# Ctrl_main10.net
KiCad netlist of a schematic drawn in EAGLE
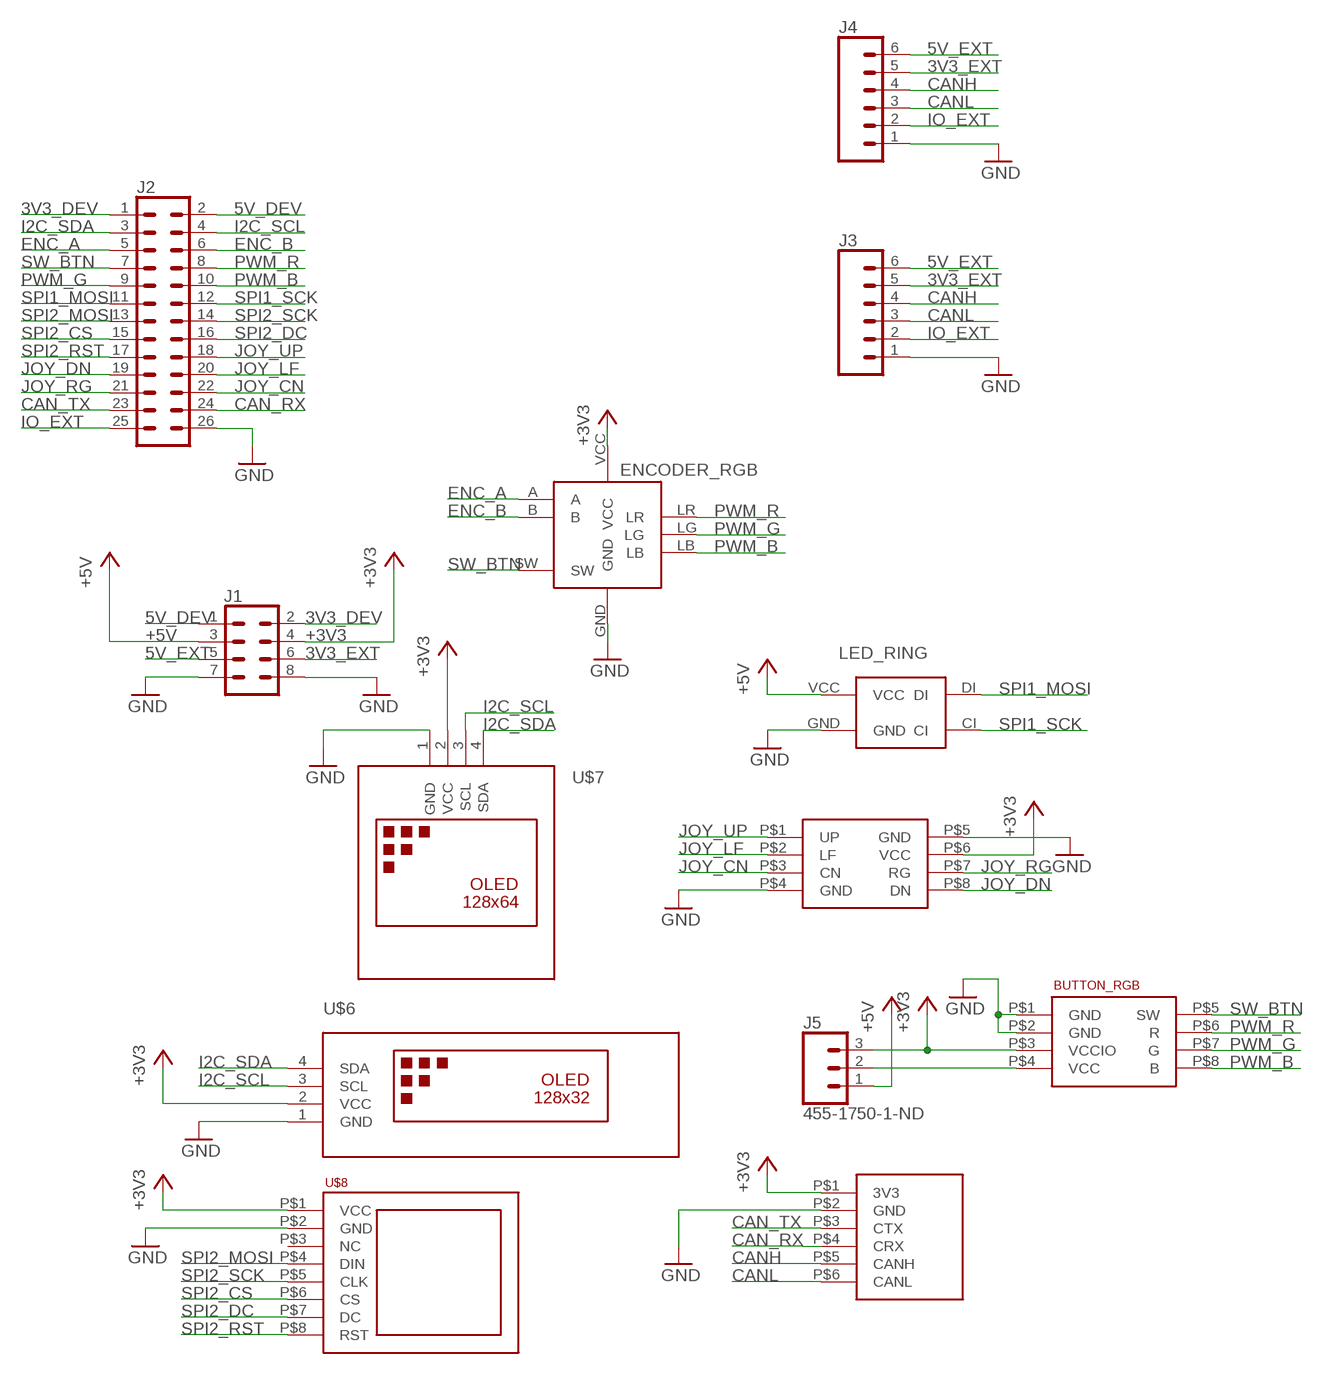
[diagram p0: schematic, sheet 1]

(export (version "E")
  (design (tool "Eeschema 10.0.6"))
  (components
    (comp (ref "BUTTON_RGB")
      (value "CTRL_BTNRGB_BRD")
      (footprint "eagle-import:CTRL_BTNRGB_BRD")
      (libsource (lib "eagle-import") (part "CTRL_BTNRGB_BRD"))
    )
    (comp (ref "ENCODER_RGB")
      (value "CTRL_ENC")
      (footprint "eagle-import:CTRL_ENC")
      (libsource (lib "eagle-import") (part "CTRL_ENC"))
    )
    (comp (ref "J1")
      (value "CONN_04X2")
      (footprint "eagle-import:2X4")
      (libsource (lib "eagle-import") (part "CONN_04X2"))
    )
    (comp (ref "J2")
      (value "CONN_13X22X13")
      (footprint "eagle-import:2X13")
      (libsource (lib "eagle-import") (part "CONN_13X22X13"))
    )
    (comp (ref "J3")
      (value "CONN_06SILK_FEMALE_PTH")
      (footprint "eagle-import:1X06")
      (libsource (lib "eagle-import") (part "CONN_06SILK_FEMALE_PTH"))
    )
    (comp (ref "J4")
      (value "CONN_06SILK_FEMALE_PTH")
      (footprint "eagle-import:1X06")
      (libsource (lib "eagle-import") (part "CONN_06SILK_FEMALE_PTH"))
    )
    (comp (ref "J5")
      (value "455-1750-1-ND")
      (footprint "eagle-import:1X03")
      (libsource (lib "eagle-import") (part "CONN_03"))
    )
    (comp (ref "LED_RING")
      (value "CTRL_RING")
      (footprint "eagle-import:CTRL_RING")
      (libsource (lib "eagle-import") (part "CTRL_RING"))
    )
    (comp (ref "U$3")
      (value "CTRL_JOY")
      (footprint "eagle-import:CTRL_JOY")
      (libsource (lib "eagle-import") (part "CTRL_JOY"))
    )
    (comp (ref "U$4")
      (value "CTRL_CAN")
      (footprint "eagle-import:CTRL_CAN")
      (libsource (lib "eagle-import") (part "CTRL_CAN"))
    )
    (comp (ref "U$6")
      (value "DISPLAY-OLED-128X32")
      (footprint "eagle-import:DISPLAY-OLED-128X32")
      (libsource (lib "eagle-import") (part "DISPLAY-OLED-128X32"))
    )
    (comp (ref "U$7")
      (value "DISPLAY-OLED-128X64-I2C")
      (footprint "eagle-import:DISPLAY-OLED-128X64-I2C")
      (libsource (lib "eagle-import") (part "DISPLAY-OLED-128X64-I2C"))
    )
    (comp (ref "U$8")
      (value "OLED_WS128")
      (footprint "eagle-import:OLED_WS128")
      (libsource (lib "eagle-import") (part "OLED_WS128"))
    )
  )
  (nets
    (net (code "1") (name "+3V3") (class "Default")
      (node (ref "BUTTON_RGB") (pin "P$3") (pinfunction "VCCIO_P$3") (pintype "bidirectional"))
      (node (ref "ENCODER_RGB") (pin "VCC") (pinfunction "VCC_VCC") (pintype "bidirectional"))
      (node (ref "J1") (pin "4") (pinfunction "4_4") (pintype "passive"))
      (node (ref "J5") (pin "3") (pinfunction "3_3") (pintype "passive"))
      (node (ref "U$3") (pin "P$6") (pinfunction "VCC_P$6") (pintype "bidirectional"))
      (node (ref "U$4") (pin "P$1") (pinfunction "3V3_P$1") (pintype "bidirectional"))
      (node (ref "U$6") (pin "2") (pinfunction "VCC_2") (pintype "power_in"))
      (node (ref "U$7") (pin "2") (pinfunction "VCC_2") (pintype "power_in"))
      (node (ref "U$8") (pin "P$1") (pinfunction "VCC_P$1") (pintype "bidirectional"))
    )
    (net (code "2") (name "+5V") (class "Default")
      (node (ref "J1") (pin "3") (pinfunction "3_3") (pintype "passive"))
      (node (ref "J5") (pin "1") (pinfunction "1_1") (pintype "passive"))
      (node (ref "LED_RING") (pin "VCC") (pinfunction "VCC_VCC") (pintype "bidirectional"))
    )
    (net (code "3") (name "/3V3_DEV") (class "Default")
      (node (ref "J1") (pin "2") (pinfunction "2_2") (pintype "passive"))
      (node (ref "J2") (pin "1") (pinfunction "1_1") (pintype "passive"))
    )
    (net (code "4") (name "/3V3_EXT") (class "Default")
      (node (ref "J1") (pin "6") (pinfunction "6_6") (pintype "passive"))
      (node (ref "J3") (pin "5") (pinfunction "5_5") (pintype "passive"))
      (node (ref "J4") (pin "5") (pinfunction "5_5") (pintype "passive"))
    )
    (net (code "5") (name "/5V_DEV") (class "Default")
      (node (ref "J1") (pin "1") (pinfunction "1_1") (pintype "passive"))
      (node (ref "J2") (pin "2") (pinfunction "2_2") (pintype "passive"))
    )
    (net (code "6") (name "/5V_EXT") (class "Default")
      (node (ref "J1") (pin "5") (pinfunction "5_5") (pintype "passive"))
      (node (ref "J3") (pin "6") (pinfunction "6_6") (pintype "passive"))
      (node (ref "J4") (pin "6") (pinfunction "6_6") (pintype "passive"))
    )
    (net (code "7") (name "/CANH") (class "Default")
      (node (ref "J3") (pin "4") (pinfunction "4_4") (pintype "passive"))
      (node (ref "J4") (pin "4") (pinfunction "4_4") (pintype "passive"))
      (node (ref "U$4") (pin "P$5") (pinfunction "CANH_P$5") (pintype "bidirectional"))
    )
    (net (code "8") (name "/CANL") (class "Default")
      (node (ref "J3") (pin "3") (pinfunction "3_3") (pintype "passive"))
      (node (ref "J4") (pin "3") (pinfunction "3_3") (pintype "passive"))
      (node (ref "U$4") (pin "P$6") (pinfunction "CANL_P$6") (pintype "bidirectional"))
    )
    (net (code "9") (name "/CAN_RX") (class "Default")
      (node (ref "J2") (pin "24") (pinfunction "24_24") (pintype "passive"))
      (node (ref "U$4") (pin "P$4") (pinfunction "CRX_P$4") (pintype "bidirectional"))
    )
    (net (code "10") (name "/CAN_TX") (class "Default")
      (node (ref "J2") (pin "23") (pinfunction "23_23") (pintype "passive"))
      (node (ref "U$4") (pin "P$3") (pinfunction "CTX_P$3") (pintype "bidirectional"))
    )
    (net (code "11") (name "/ENC_A") (class "Default")
      (node (ref "ENCODER_RGB") (pin "A") (pinfunction "A_A") (pintype "bidirectional"))
      (node (ref "J2") (pin "5") (pinfunction "5_5") (pintype "passive"))
    )
    (net (code "12") (name "/ENC_B") (class "Default")
      (node (ref "ENCODER_RGB") (pin "B") (pinfunction "B_B") (pintype "bidirectional"))
      (node (ref "J2") (pin "6") (pinfunction "6_6") (pintype "passive"))
    )
    (net (code "13") (name "/I2C_SCL") (class "Default")
      (node (ref "J2") (pin "4") (pinfunction "4_4") (pintype "passive"))
      (node (ref "U$6") (pin "3") (pinfunction "SCL_3") (pintype "bidirectional"))
      (node (ref "U$7") (pin "3") (pinfunction "SCL_3") (pintype "bidirectional"))
    )
    (net (code "14") (name "/I2C_SDA") (class "Default")
      (node (ref "J2") (pin "3") (pinfunction "3_3") (pintype "passive"))
      (node (ref "U$6") (pin "4") (pinfunction "SDA_4") (pintype "bidirectional"))
      (node (ref "U$7") (pin "4") (pinfunction "SDA_4") (pintype "bidirectional"))
    )
    (net (code "15") (name "/IO_EXT") (class "Default")
      (node (ref "J2") (pin "25") (pinfunction "25_25") (pintype "passive"))
      (node (ref "J3") (pin "2") (pinfunction "2_2") (pintype "passive"))
      (node (ref "J4") (pin "2") (pinfunction "2_2") (pintype "passive"))
    )
    (net (code "16") (name "/JOY_CN") (class "Default")
      (node (ref "J2") (pin "22") (pinfunction "22_22") (pintype "passive"))
      (node (ref "U$3") (pin "P$3") (pinfunction "CN_P$3") (pintype "bidirectional"))
    )
    (net (code "17") (name "/JOY_DN") (class "Default")
      (node (ref "J2") (pin "19") (pinfunction "19_19") (pintype "passive"))
      (node (ref "U$3") (pin "P$8") (pinfunction "DN_P$8") (pintype "bidirectional"))
    )
    (net (code "18") (name "/JOY_LF") (class "Default")
      (node (ref "J2") (pin "20") (pinfunction "20_20") (pintype "passive"))
      (node (ref "U$3") (pin "P$2") (pinfunction "LF_P$2") (pintype "bidirectional"))
    )
    (net (code "19") (name "/JOY_RG") (class "Default")
      (node (ref "J2") (pin "21") (pinfunction "21_21") (pintype "passive"))
      (node (ref "U$3") (pin "P$7") (pinfunction "RG_P$7") (pintype "bidirectional"))
    )
    (net (code "20") (name "/JOY_UP") (class "Default")
      (node (ref "J2") (pin "18") (pinfunction "18_18") (pintype "passive"))
      (node (ref "U$3") (pin "P$1") (pinfunction "UP_P$1") (pintype "bidirectional"))
    )
    (net (code "21") (name "/PWM_B") (class "Default")
      (node (ref "BUTTON_RGB") (pin "P$8") (pinfunction "B_P$8") (pintype "bidirectional"))
      (node (ref "ENCODER_RGB") (pin "LB") (pinfunction "LB_LB") (pintype "bidirectional"))
      (node (ref "J2") (pin "10") (pinfunction "10_10") (pintype "passive"))
    )
    (net (code "22") (name "/PWM_G") (class "Default")
      (node (ref "BUTTON_RGB") (pin "P$7") (pinfunction "G_P$7") (pintype "bidirectional"))
      (node (ref "ENCODER_RGB") (pin "LG") (pinfunction "LG_LG") (pintype "bidirectional"))
      (node (ref "J2") (pin "9") (pinfunction "9_9") (pintype "passive"))
    )
    (net (code "23") (name "/PWM_R") (class "Default")
      (node (ref "BUTTON_RGB") (pin "P$6") (pinfunction "R_P$6") (pintype "bidirectional"))
      (node (ref "ENCODER_RGB") (pin "LR") (pinfunction "LR_LR") (pintype "bidirectional"))
      (node (ref "J2") (pin "8") (pinfunction "8_8") (pintype "passive"))
    )
    (net (code "24") (name "/SPI1_MOSI") (class "Default")
      (node (ref "J2") (pin "11") (pinfunction "11_11") (pintype "passive"))
      (node (ref "LED_RING") (pin "DI") (pinfunction "DI_DI") (pintype "bidirectional"))
    )
    (net (code "25") (name "/SPI1_SCK") (class "Default")
      (node (ref "J2") (pin "12") (pinfunction "12_12") (pintype "passive"))
      (node (ref "LED_RING") (pin "CI") (pinfunction "CI_CI") (pintype "bidirectional"))
    )
    (net (code "26") (name "/SPI2_CS") (class "Default")
      (node (ref "J2") (pin "15") (pinfunction "15_15") (pintype "passive"))
      (node (ref "U$8") (pin "P$6") (pinfunction "CS_P$6") (pintype "bidirectional"))
    )
    (net (code "27") (name "/SPI2_DC") (class "Default")
      (node (ref "J2") (pin "16") (pinfunction "16_16") (pintype "passive"))
      (node (ref "U$8") (pin "P$7") (pinfunction "DC_P$7") (pintype "bidirectional"))
    )
    (net (code "28") (name "/SPI2_MOSI") (class "Default")
      (node (ref "J2") (pin "13") (pinfunction "13_13") (pintype "passive"))
      (node (ref "U$8") (pin "P$4") (pinfunction "DIN_P$4") (pintype "bidirectional"))
    )
    (net (code "29") (name "/SPI2_RST") (class "Default")
      (node (ref "J2") (pin "17") (pinfunction "17_17") (pintype "passive"))
      (node (ref "U$8") (pin "P$8") (pinfunction "RST_P$8") (pintype "bidirectional"))
    )
    (net (code "30") (name "/SPI2_SCK") (class "Default")
      (node (ref "J2") (pin "14") (pinfunction "14_14") (pintype "passive"))
      (node (ref "U$8") (pin "P$5") (pinfunction "CLK_P$5") (pintype "bidirectional"))
    )
    (net (code "31") (name "/SW_BTN") (class "Default")
      (node (ref "BUTTON_RGB") (pin "P$5") (pinfunction "SW_P$5") (pintype "bidirectional"))
      (node (ref "ENCODER_RGB") (pin "SW") (pinfunction "SW_SW") (pintype "bidirectional"))
      (node (ref "J2") (pin "7") (pinfunction "7_7") (pintype "passive"))
    )
    (net (code "32") (name "GND") (class "Default")
      (node (ref "BUTTON_RGB") (pin "P$1") (pinfunction "GND_P$1") (pintype "bidirectional"))
      (node (ref "BUTTON_RGB") (pin "P$2") (pinfunction "GND_P$2") (pintype "bidirectional"))
      (node (ref "ENCODER_RGB") (pin "GND") (pinfunction "GND_GND") (pintype "bidirectional"))
      (node (ref "J1") (pin "7") (pinfunction "7_7") (pintype "passive"))
      (node (ref "J1") (pin "8") (pinfunction "8_8") (pintype "passive"))
      (node (ref "J2") (pin "26") (pinfunction "26_26") (pintype "passive"))
      (node (ref "J3") (pin "1") (pinfunction "1_1") (pintype "passive"))
      (node (ref "J4") (pin "1") (pinfunction "1_1") (pintype "passive"))
      (node (ref "LED_RING") (pin "GND") (pinfunction "GND_GND") (pintype "bidirectional"))
      (node (ref "U$3") (pin "P$4") (pinfunction "GND_P$4") (pintype "bidirectional"))
      (node (ref "U$3") (pin "P$5") (pinfunction "GND_P$5") (pintype "bidirectional"))
      (node (ref "U$4") (pin "P$2") (pinfunction "GND_P$2") (pintype "bidirectional"))
      (node (ref "U$6") (pin "1") (pinfunction "GND_1") (pintype "power_in"))
      (node (ref "U$7") (pin "1") (pinfunction "GND_1") (pintype "power_in"))
      (node (ref "U$8") (pin "P$2") (pinfunction "GND_P$2") (pintype "bidirectional"))
    )
    (net (code "33") (name "Net-(BUTTON_RGB-VCC)") (class "Default")
      (node (ref "BUTTON_RGB") (pin "P$4") (pinfunction "VCC_P$4") (pintype "bidirectional"))
      (node (ref "J5") (pin "2") (pinfunction "2_2") (pintype "passive"))
    )
    (net (code "34") (name "unconnected-(U$8-NC-PadP$3)") (class "Default")
      (node (ref "U$8") (pin "P$3") (pinfunction "NC_P$3") (pintype "no_connect"))
    )
  )
)
